# Scheme_E-button_1.net
KiCad netlist of a schematic drawn in Altium Designer
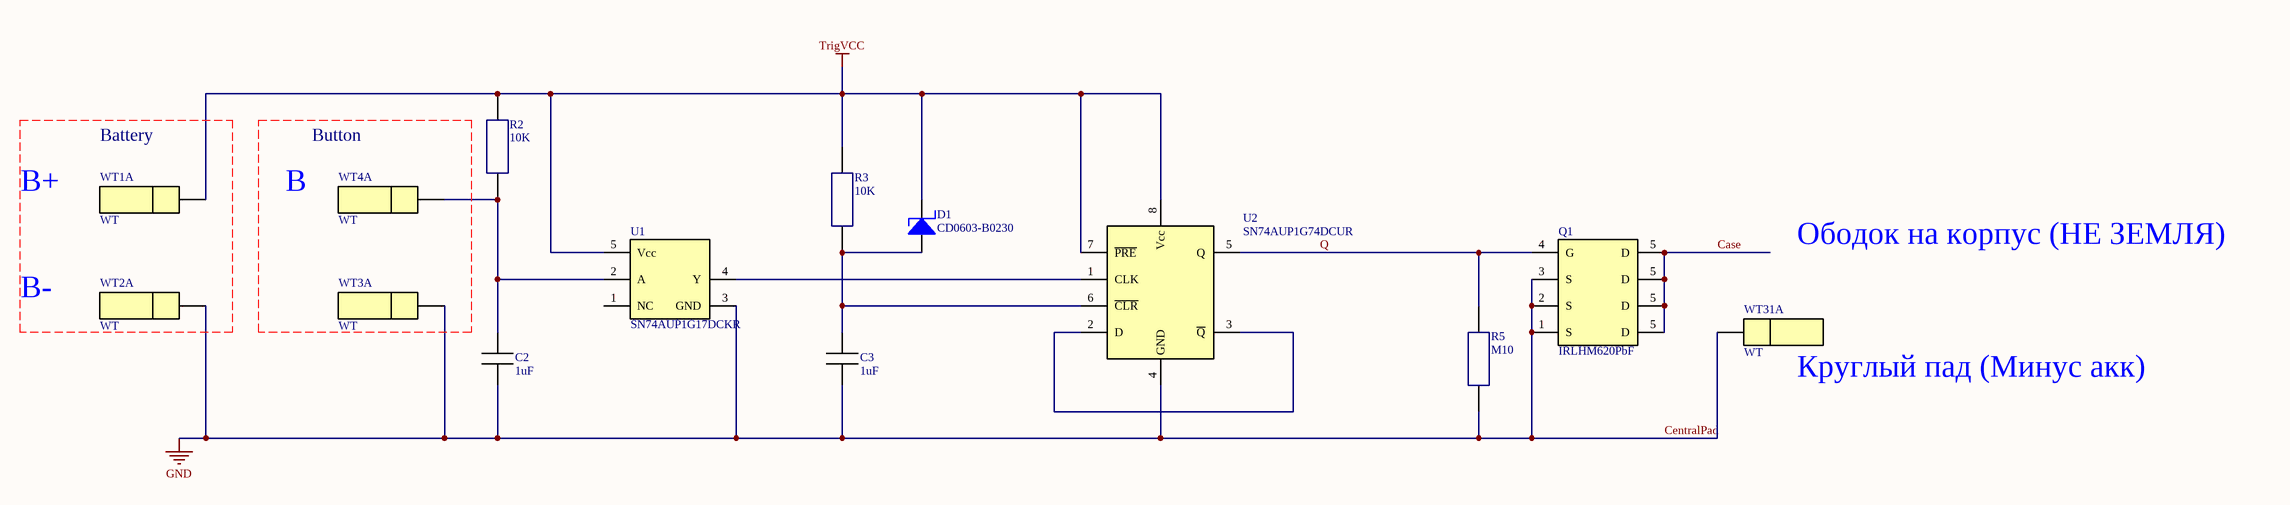
[diagram p0: Scheme_E-button(1).SchDoc]

(export (version "E")
  (design (tool "Eeschema 10.0.6"))
  (components
    (comp (ref "C2")
      (value "1uF")
      (footprint "Cap 0603")
      (description "C 1uF  x 25V")
      (fields (field (name "VOLTAGE") "25V") (field (name "Comment") "1u0"))
      (libsource (lib "Altium Vault") (part "Capasitor Ceramic"))
    )
    (comp (ref "C3")
      (value "1uF")
      (footprint "Cap 0603")
      (description "C 1uF  x 25V")
      (fields (field (name "VOLTAGE") "25V") (field (name "Comment") "1u0"))
      (libsource (lib "Altium Vault") (part "Capasitor Ceramic"))
    )
    (comp (ref "D1")
      (value "CD0603-B0230")
      (footprint "0603")
      (fields (field (name "Comment") "B5"))
      (libsource (lib "Altium Vault") (part "Schottky diode"))
    )
    (comp (ref "Q1")
      (value "IRLHM620PbF")
      (footprint "PQFN-8 3.3x3.3")
      (fields (field (name "Comment") "IRLHM620"))
      (libsource (lib "Altium Vault") (part "IRLHM620PbF"))
    )
    (comp (ref "R2")
      (value "10K")
      (footprint "R0603 5%")
      (description "R 10K")
      (fields (field (name "Comment") "103"))
      (libsource (lib "Altium Vault") (part "Resistors"))
    )
    (comp (ref "R3")
      (value "10K")
      (footprint "R0603 5%")
      (description "R 10K")
      (fields (field (name "Comment") "103"))
      (libsource (lib "Altium Vault") (part "Resistors"))
    )
    (comp (ref "R5")
      (value "M10")
      (footprint "R0603 5%")
      (description "R M10")
      (fields (field (name "Comment") "104"))
      (libsource (lib "Altium Vault") (part "Resistors"))
    )
    (comp (ref "U1")
      (value "SN74AUP1G17DCKR")
      (footprint "SC-70-5")
      (fields (field (name "Comment") "SN74AUP"))
      (libsource (lib "Altium Vault") (part "SN74AUP1G17DCKR"))
    )
    (comp (ref "U2")
      (value "SN74AUP1G74DCUR")
      (footprint "VSSOP-8 2.3x2.3mm")
      (fields (field (name "Comment") "SN74AUP"))
      (libsource (lib "Altium Vault") (part "SN74AUP1G74DCUR"))
    )
    (comp (ref "WT1") (value "WT") (footprint "WT") (libsource (lib "Altium Vault") (part "WireTerminal")))
    (comp (ref "WT2") (value "WT") (footprint "WT") (libsource (lib "Altium Vault") (part "WireTerminal")))
    (comp (ref "WT3") (value "WT") (footprint "WT") (libsource (lib "Altium Vault") (part "CMP-00159-3")))
    (comp (ref "WT4") (value "WT") (footprint "WT") (libsource (lib "Altium Vault") (part "CMP-00159-3")))
    (comp (ref "WT31") (value "WT") (footprint "WT") (libsource (lib "") (part "CMP-00159-3_1")))
  )
  (nets
    (net (code "1") (name "/Case") (class "Default")
      (node (ref "Q1") (pin "5") (pinfunction "D_5") (pintype "passive"))
    )
    (net (code "2") (name "/Q") (class "Default")
      (node (ref "Q1") (pin "4") (pinfunction "G_4") (pintype "passive"))
      (node (ref "R5") (pin "2") (pinfunction "2_2") (pintype "passive"))
      (node (ref "U2") (pin "5") (pinfunction "Q_5") (pintype "passive"))
    )
    (net (code "3") (name "GND") (class "Default")
      (node (ref "C2") (pin "1") (pinfunction "1_1") (pintype "passive"))
      (node (ref "C3") (pin "1") (pinfunction "1_1") (pintype "passive"))
      (node (ref "Q1") (pin "1") (pinfunction "S_1") (pintype "passive"))
      (node (ref "Q1") (pin "2") (pinfunction "S_2") (pintype "passive"))
      (node (ref "Q1") (pin "3") (pinfunction "S_3") (pintype "passive"))
      (node (ref "R5") (pin "1") (pinfunction "1_1") (pintype "passive"))
      (node (ref "U1") (pin "3") (pinfunction "GND_3") (pintype "passive"))
      (node (ref "U2") (pin "4") (pinfunction "GND_4") (pintype "passive"))
      (node (ref "WT2") (pin "1") (pinfunction "1_1") (pintype "passive"))
      (node (ref "WT3") (pin "1") (pinfunction "1_1") (pintype "passive"))
      (node (ref "WT31") (pin "1") (pinfunction "1_1") (pintype "passive"))
    )
    (net (code "4") (name "Net-(U1-A)") (class "Default")
      (node (ref "C2") (pin "2") (pinfunction "2_2") (pintype "passive"))
      (node (ref "R2") (pin "2") (pinfunction "2_2") (pintype "passive"))
      (node (ref "U1") (pin "2") (pinfunction "A_2") (pintype "passive"))
      (node (ref "WT4") (pin "1") (pinfunction "1_1") (pintype "passive"))
    )
    (net (code "5") (name "Net-(U1-Y)") (class "Default")
      (node (ref "U1") (pin "4") (pinfunction "Y_4") (pintype "passive"))
      (node (ref "U2") (pin "1") (pinfunction "CLK_1") (pintype "passive"))
    )
    (net (code "6") (name "Net-(U2-D)") (class "Default")
      (node (ref "U2") (pin "2") (pinfunction "D_2") (pintype "passive"))
      (node (ref "U2") (pin "3") (pinfunction "~{Q}_3") (pintype "passive"))
    )
    (net (code "7") (name "Net-(U2-~{CLR})") (class "Default")
      (node (ref "C3") (pin "2") (pinfunction "2_2") (pintype "passive"))
      (node (ref "D1") (pin "2") (pinfunction "2_2") (pintype "passive"))
      (node (ref "R3") (pin "2") (pinfunction "2_2") (pintype "passive"))
      (node (ref "U2") (pin "6") (pinfunction "~{CLR}_6") (pintype "passive"))
    )
    (net (code "8") (name "TrigVCC") (class "Default")
      (node (ref "D1") (pin "1") (pinfunction "1_1") (pintype "passive"))
      (node (ref "R2") (pin "1") (pinfunction "1_1") (pintype "passive"))
      (node (ref "R3") (pin "1") (pinfunction "1_1") (pintype "passive"))
      (node (ref "U1") (pin "5") (pinfunction "Vcc_5") (pintype "passive"))
      (node (ref "U2") (pin "7") (pinfunction "~{PRE}_7") (pintype "passive"))
      (node (ref "U2") (pin "8") (pinfunction "Vcc_8") (pintype "passive"))
      (node (ref "WT1") (pin "1") (pinfunction "1_1") (pintype "passive"))
    )
    (net (code "9") (name "unconnected-(U1-NC-Pad1)") (class "Default")
      (node (ref "U1") (pin "1") (pinfunction "NC_1") (pintype "passive"))
    )
  )
)
